# 1_POWER.net
KiCad netlist of a schematic drawn in Altium Designer
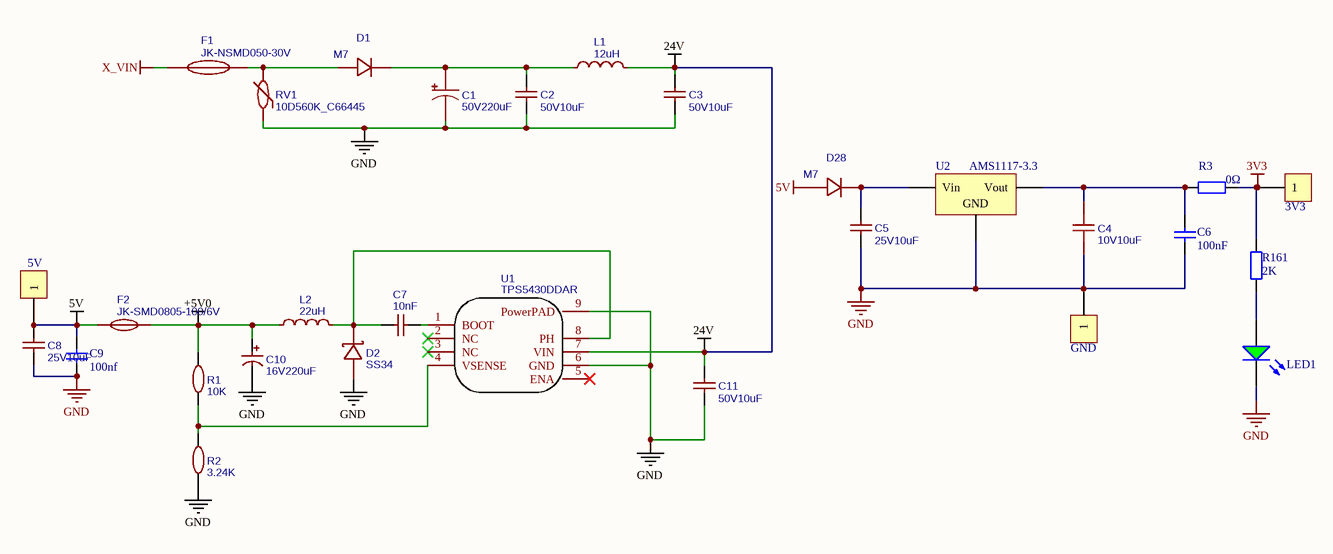
[diagram p0: 1.POWER.SchDoc]

(export (version "E")
  (design (tool "Eeschema 10.0.6"))
  (components
    (comp (ref "3V3")
      (value "TST3V3")
      (footprint "Con-TEST-VCC")
      (description "Connector")
      (libsource (lib "") (part "CON1_1"))
    )
    (comp (ref "5V")
      (value "TST5V")
      (footprint "Con-TEST-VCC")
      (description "Connector")
      (libsource (lib "*") (part "CON1"))
    )
    (comp (ref "C1")
      (value "50V220uF")
      (footprint "CAP-SMD_BD10.0-L10.3-W10.3-FD")
      (fields
        (field (name "BOM_SUPPLIER PART") "C125977")
        (field (name "BOM_MANUFACTURER PART") "UWT1H221MNL1GS")
        (field (name "CONTRIBUTOR") "LCSC")
      )
      (libsource (lib "altium-import") (part "root_0_220uF_"))
    )
    (comp (ref "C2")
      (value "50V10uF")
      (footprint "C1206")
      (description "贴片电容")
      (fields
        (field (name "BOM_MANUFACTURER PART") "CL31A106KBHNNNE")
        (field (name "BOM_SUPPLIER PART") "C13585")
      )
      (libsource (lib "altium-import") (part "root_1_10uF_"))
    )
    (comp (ref "C3")
      (value "50V10uF")
      (footprint "C1206")
      (description "贴片电容")
      (fields
        (field (name "BOM_MANUFACTURER PART") "CL31A106KBHNNNE")
        (field (name "BOM_SUPPLIER PART") "C13585")
      )
      (libsource (lib "altium-import") (part "root_1_10uF_"))
    )
    (comp (ref "C4")
      (value "10V10uF")
      (footprint "C0603-M")
      (description "贴片电容")
      (fields
        (field (name "BOM_MANUFACTURER PART") "CL10A106KP8NNNC")
        (field (name "BOM_SUPPLIER PART") "C19702")
      )
      (libsource (lib "") (part "root_1_10uF__1"))
    )
    (comp (ref "C5")
      (value "25V10uF")
      (footprint "C0805")
      (description "贴片电容")
      (fields
        (field (name "BOM_MANUFACTURER PART") "CL21A106KOQNNNE")
        (field (name "BOM_SUPPLIER PART") "C15850")
      )
      (libsource (lib "altium-import") (part "root_1_10uF_"))
    )
    (comp (ref "C6")
      (value "100nF")
      (footprint "C0603-M")
      (description "贴片电容")
      (fields (field (name "PUBLISHER") "Altium Limited"))
      (libsource (lib "Miscellaneous Devices") (part "Cap Semi"))
    )
    (comp (ref "C7")
      (value "10nF")
      (footprint "C0603")
      (fields
        (field (name "BOM_MANUFACTURER PART") "0603B103K500NT")
        (field (name "BOM_SUPPLIER PART") "C57112")
      )
      (libsource (lib "altium-import") (part "root_0_10nF_"))
    )
    (comp (ref "C8")
      (value "25V10uF")
      (footprint "C0805")
      (description "贴片电容")
      (fields
        (field (name "BOM_MANUFACTURER PART") "CL21A106KOQNNNE")
        (field (name "BOM_SUPPLIER PART") "C15850")
      )
      (libsource (lib "altium-import") (part "root_1_10uF_"))
    )
    (comp (ref "C9")
      (value "100nf")
      (footprint "C0603-M")
      (description "Capacitor")
      (fields (field (name "Comment") "100nF") (field (name "PUBLISHER") "Altium Limited"))
      (libsource (lib "SUPERWDS") (part "Cap1"))
    )
    (comp (ref "C10")
      (value "16V220uF")
      (footprint "CAP-SMD_BD6.3-L6.6-W6.6-FD")
      (description "贴片电解电容")
      (fields
        (field (name "BOM_MANUFACTURER PART") "ZV221M016E077R")
        (field (name "BOM_SUPPLIER PART") "C65226")
      )
      (libsource (lib "altium-import") (part "root_3_220uF_"))
    )
    (comp (ref "C11")
      (value "50V10uF")
      (footprint "C1206")
      (description "贴片电容")
      (fields
        (field (name "BOM_MANUFACTURER PART") "CL31A106KBHNNNE")
        (field (name "BOM_SUPPLIER PART") "C13585")
      )
      (libsource (lib "altium-import") (part "root_1_10uF_"))
    )
    (comp (ref "D1")
      (value "M7")
      (footprint "SMA_L4.4-W2.6-LS5.0-RD")
      (description "通用二极管")
      (fields (field (name "BOM_SUPPLIER PART") "C95872") (field (name "CONTRIBUTOR") "LCSC"))
      (libsource (lib "altium-import") (part "root_2_M7_C426571_"))
    )
    (comp (ref "D2")
      (value "SS34")
      (footprint "SMA_L4.3-W2.6-LS5.2-RD")
      (description "肖特基二极管")
      (fields (field (name "BOM_MANUFACTURER PART") "B340A") (field (name "BOM_SUPPLIER PART") "C8678"))
      (libsource (lib "altium-import") (part "root_3_B340A_"))
    )
    (comp (ref "D28")
      (value "M7")
      (footprint "SMA_L4.4-W2.6-LS5.0-RD")
      (description "通用二极管")
      (fields (field (name "BOM_SUPPLIER PART") "C95872") (field (name "CONTRIBUTOR") "LCSC"))
      (libsource (lib "altium-import") (part "root_2_M7_C426571_"))
    )
    (comp (ref "F1")
      (value "JK-NSMD050-30V")
      (footprint "F1206")
      (fields (field (name "BOM_SUPPLIER PART") "C720075") (field (name "CONTRIBUTOR") "LCSC"))
      (libsource (lib "altium-import") (part "root_0_JK-NSMD050-30V_"))
    )
    (comp (ref "F2")
      (value "JK-SMD0805-100/6V")
      (footprint "F0805")
      (fields (field (name "BOM_SUPPLIER PART") "C2830233") (field (name "CONTRIBUTOR") "LCSC"))
      (libsource (lib "altium-import") (part "root_0_JK-SMD0805-100/6V_"))
    )
    (comp (ref "GND")
      (value "GND")
      (footprint "Con-TEST-VCC")
      (description "Connector")
      (libsource (lib "") (part "CON1_2"))
    )
    (comp (ref "L1")
      (value "12uH")
      (footprint "IND-SMD_L4.0-W4.0_SWPA4018S")
      (fields
        (field (name "BOM_SUPPLIER PART") "C96892")
        (field (name "BOM_MANUFACTURER PART") "SWPA4030S120MT")
        (field (name "CONTRIBUTOR") "LCSC")
      )
      (libsource (lib "altium-import") (part "root_0_12uH_"))
    )
    (comp (ref "L2")
      (value "22uH")
      (footprint "IND-SMD_L7.1-W6.6")
      (fields
        (field (name "BOM_SUPPLIER PART") "C497873")
        (field (name "BOM_MANUFACTURER PART") "YSPI0630A-220M")
        (field (name "CONTRIBUTOR") "LCSC")
      )
      (libsource (lib "altium-import") (part "root_0_22uH_"))
    )
    (comp (ref "LED1")
      (value "绿灯 0603")
      (footprint "0603_LED_S1")
      (description "发光二极管")
      (libsource (lib "Miscellaneous Devices LC") (part "0603 绿灯"))
    )
    (comp (ref "R1")
      (value "10K")
      (footprint "R0603")
      (fields
        (field (name "BOM_MANUFACTURER PART") "0603WAF1002T5E")
        (field (name "BOM_SUPPLIER PART") "C25804")
      )
      (libsource (lib "altium-import") (part "root_1_10kΩ_"))
    )
    (comp (ref "R2")
      (value "3.24K")
      (footprint "R0603")
      (fields
        (field (name "BOM_MANUFACTURER PART") "0603WAF3241T5E")
        (field (name "BOM_SUPPLIER PART") "C22994")
      )
      (libsource (lib "altium-import") (part "root_1_3.24kΩ_"))
    )
    (comp (ref "R3")
      (value "0Ω")
      (footprint "R0603-M")
      (description "贴片电阻/0Ω")
      (fields (field (name "PUBLISHER") "Altium Limited"))
      (libsource (lib "Miscellaneous Devices") (part "Res2"))
    )
    (comp (ref "R161")
      (value "2K")
      (footprint "R0603-M")
      (description "贴片电阻")
      (fields (field (name "PUBLISHER") "Altium Limited"))
      (libsource (lib "") (part "Res2_1"))
    )
    (comp (ref "RV1")
      (value "10D560K_C66445")
      (footprint "RES-TH_L12.5-W4.0-P7.50-D1.0")
      (fields (field (name "BOM_MANUFACTURER PART") "10D560K") (field (name "BOM_SUPPLIER PART") "C66445"))
      (libsource (lib "altium-import") (part "root_1_10D560K_C66445_"))
    )
    (comp (ref "U1")
      (value "TPS5430DDAR")
      (footprint "SOIC-8_L5.0-W4.0-P1.27-LS6.0-BL-EP2.0")
      (fields (field (name "BOM_SUPPLIER PART") "C9864"))
      (libsource (lib "altium-import") (part "root_0_TPS5430DDAR_"))
    )
    (comp (ref "U2")
      (value "AMS1117-3.3")
      (footprint "SOT-223")
      (description "低压差线性稳压(LDO)")
      (libsource (lib "Miscellaneous Devices LC") (part "SOT-223 AMS1117-3.3"))
    )
  )
  (nets
    (net (code "1") (name "+5V0") (class "Default")
      (node (ref "C10") (pin "1") (pinfunction "1_1") (pintype "passive"))
      (node (ref "F2") (pin "2") (pinfunction "2_2") (pintype "passive"))
      (node (ref "L2") (pin "1") (pinfunction "1_1") (pintype "passive"))
      (node (ref "R1") (pin "2") (pinfunction "2_2") (pintype "passive"))
    )
    (net (code "2") (name "3V3") (class "Default")
      (node (ref "3V3") (pin "1") (pinfunction "1_1") (pintype "passive"))
      (node (ref "R161") (pin "2") (pinfunction "2_2") (pintype "passive"))
      (node (ref "R3") (pin "1") (pinfunction "1_1") (pintype "passive"))
    )
    (net (code "3") (name "5V") (class "Default")
      (node (ref "5V") (pin "1") (pinfunction "1_1") (pintype "passive"))
      (node (ref "C8") (pin "2") (pinfunction "2_2") (pintype "passive"))
      (node (ref "C9") (pin "2") (pinfunction "2_2") (pintype "passive"))
      (node (ref "D28") (pin "2") (pinfunction "A_2") (pintype "passive"))
      (node (ref "F2") (pin "1") (pinfunction "1_1") (pintype "passive"))
    )
    (net (code "4") (name "24V") (class "Default")
      (node (ref "C11") (pin "2") (pinfunction "2_2") (pintype "passive"))
      (node (ref "C3") (pin "2") (pinfunction "2_2") (pintype "passive"))
      (node (ref "L1") (pin "2") (pinfunction "2_2") (pintype "passive"))
      (node (ref "U1") (pin "7") (pinfunction "VIN_7") (pintype "passive"))
    )
    (net (code "5") (name "GND") (class "Default")
      (node (ref "C1") (pin "2") (pinfunction "2_2") (pintype "passive"))
      (node (ref "C10") (pin "2") (pinfunction "2_2") (pintype "passive"))
      (node (ref "C11") (pin "1") (pinfunction "1_1") (pintype "passive"))
      (node (ref "C2") (pin "1") (pinfunction "1_1") (pintype "passive"))
      (node (ref "C3") (pin "1") (pinfunction "1_1") (pintype "passive"))
      (node (ref "C4") (pin "1") (pinfunction "1_1") (pintype "passive"))
      (node (ref "C5") (pin "1") (pinfunction "1_1") (pintype "passive"))
      (node (ref "C6") (pin "1") (pinfunction "1_1") (pintype "passive"))
      (node (ref "C8") (pin "1") (pinfunction "1_1") (pintype "passive"))
      (node (ref "C9") (pin "1") (pinfunction "1_1") (pintype "passive"))
      (node (ref "D2") (pin "2") (pinfunction "A_2") (pintype "passive"))
      (node (ref "GND") (pin "1") (pinfunction "1_1") (pintype "passive"))
      (node (ref "LED1") (pin "K") (pinfunction "K_K") (pintype "passive"))
      (node (ref "R2") (pin "1") (pinfunction "1_1") (pintype "passive"))
      (node (ref "RV1") (pin "1") (pinfunction "1_1") (pintype "passive"))
      (node (ref "U1") (pin "6") (pinfunction "GND_6") (pintype "passive"))
      (node (ref "U1") (pin "9") (pinfunction "PowerPAD_9") (pintype "passive"))
      (node (ref "U2") (pin "1") (pinfunction "GND_1") (pintype "passive"))
    )
    (net (code "6") (name "Net-(D1-A)") (class "Default")
      (node (ref "D1") (pin "2") (pinfunction "A_2") (pintype "passive"))
      (node (ref "F1") (pin "2") (pinfunction "2_2") (pintype "passive"))
      (node (ref "RV1") (pin "2") (pinfunction "2_2") (pintype "passive"))
    )
    (net (code "7") (name "Net-(D1-C)") (class "Default")
      (node (ref "C1") (pin "1") (pinfunction "1_1") (pintype "passive"))
      (node (ref "C2") (pin "2") (pinfunction "2_2") (pintype "passive"))
      (node (ref "D1") (pin "1") (pinfunction "C_1") (pintype "passive"))
      (node (ref "L1") (pin "1") (pinfunction "1_1") (pintype "passive"))
    )
    (net (code "8") (name "Net-(D2-K)") (class "Default")
      (node (ref "C7") (pin "1") (pinfunction "1_1") (pintype "passive"))
      (node (ref "D2") (pin "1") (pinfunction "K_1") (pintype "passive"))
      (node (ref "L2") (pin "2") (pinfunction "2_2") (pintype "passive"))
      (node (ref "U1") (pin "8") (pinfunction "PH_8") (pintype "passive"))
    )
    (net (code "9") (name "Net-(D28-C)") (class "Default")
      (node (ref "C5") (pin "2") (pinfunction "2_2") (pintype "passive"))
      (node (ref "D28") (pin "1") (pinfunction "C_1") (pintype "passive"))
      (node (ref "U2") (pin "3") (pinfunction "Vin_3") (pintype "passive"))
    )
    (net (code "10") (name "Net-(LED1-PadA)") (class "Default")
      (node (ref "LED1") (pin "A") (pinfunction "A_A") (pintype "passive"))
      (node (ref "R161") (pin "1") (pinfunction "1_1") (pintype "passive"))
    )
    (net (code "11") (name "Net-(U1-BOOT)") (class "Default")
      (node (ref "C7") (pin "2") (pinfunction "2_2") (pintype "passive"))
      (node (ref "U1") (pin "1") (pinfunction "BOOT_1") (pintype "passive"))
    )
    (net (code "12") (name "Net-(U1-VSENSE)") (class "Default")
      (node (ref "R1") (pin "1") (pinfunction "1_1") (pintype "passive"))
      (node (ref "R2") (pin "2") (pinfunction "2_2") (pintype "passive"))
      (node (ref "U1") (pin "4") (pinfunction "VSENSE_4") (pintype "passive"))
    )
    (net (code "13") (name "Net-(U2-Vout)") (class "Default")
      (node (ref "C4") (pin "2") (pinfunction "2_2") (pintype "passive"))
      (node (ref "C6") (pin "2") (pinfunction "2_2") (pintype "passive"))
      (node (ref "R3") (pin "2") (pinfunction "2_2") (pintype "passive"))
      (node (ref "U2") (pin "2") (pinfunction "Vout_2") (pintype "passive"))
    )
    (net (code "14") (name "X_VIN") (class "Default")
      (node (ref "F1") (pin "1") (pinfunction "1_1") (pintype "passive"))
    )
    (net (code "15") (name "unconnected-(U1-ENA-Pad5)") (class "Default")
      (node (ref "U1") (pin "5") (pinfunction "ENA_5") (pintype "passive+no_connect"))
    )
    (net (code "16") (name "unconnected-(U1-NC-Pad2)") (class "Default")
      (node (ref "U1") (pin "2") (pinfunction "NC_2") (pintype "passive+no_connect"))
    )
    (net (code "17") (name "unconnected-(U1-NC-Pad3)") (class "Default")
      (node (ref "U1") (pin "3") (pinfunction "NC_3") (pintype "passive+no_connect"))
    )
  )
)
